# IRComms.net
KiCad netlist of a schematic drawn in Altium Designer
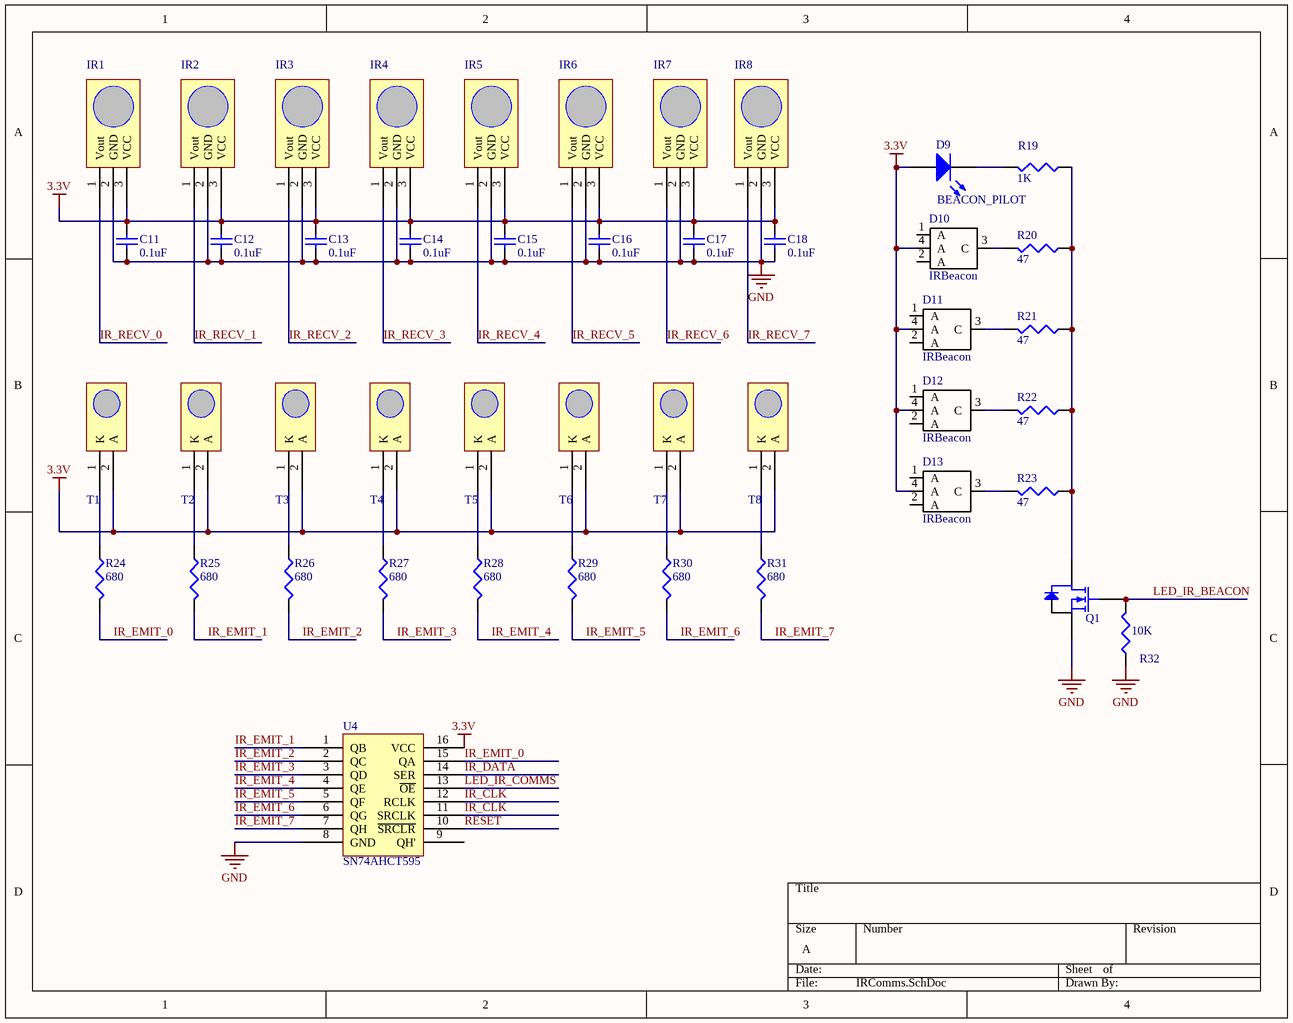
[diagram p0: IRComms.SchDoc]

(export (version "E")
  (design (tool "Eeschema 10.0.6"))
  (components
    (comp (ref "C11")
      (value "0.1uF")
      (footprint "CAPC1005L")
      (description "Capacitor (Semiconductor SIM Model)")
      (fields (field (name "Comment") "Cap Semi") (field (name "PUBLISHER") "Altium Limited"))
      (libsource (lib "Miscellaneous Devices") (part "Cap Semi"))
    )
    (comp (ref "C12")
      (value "0.1uF")
      (footprint "CAPC1005L")
      (description "Capacitor (Semiconductor SIM Model)")
      (fields (field (name "Comment") "Cap Semi") (field (name "PUBLISHER") "Altium Limited"))
      (libsource (lib "Miscellaneous Devices") (part "Cap Semi"))
    )
    (comp (ref "C13")
      (value "0.1uF")
      (footprint "CAPC1005L")
      (description "Capacitor (Semiconductor SIM Model)")
      (fields (field (name "Comment") "Cap Semi") (field (name "PUBLISHER") "Altium Limited"))
      (libsource (lib "Miscellaneous Devices") (part "Cap Semi"))
    )
    (comp (ref "C14")
      (value "0.1uF")
      (footprint "CAPC1005L")
      (description "Capacitor (Semiconductor SIM Model)")
      (fields (field (name "Comment") "Cap Semi") (field (name "PUBLISHER") "Altium Limited"))
      (libsource (lib "Miscellaneous Devices") (part "Cap Semi"))
    )
    (comp (ref "C15")
      (value "0.1uF")
      (footprint "CAPC1005L")
      (description "Capacitor (Semiconductor SIM Model)")
      (fields (field (name "Comment") "Cap Semi") (field (name "PUBLISHER") "Altium Limited"))
      (libsource (lib "Miscellaneous Devices") (part "Cap Semi"))
    )
    (comp (ref "C16")
      (value "0.1uF")
      (footprint "CAPC1005L")
      (description "Capacitor (Semiconductor SIM Model)")
      (fields (field (name "Comment") "Cap Semi") (field (name "PUBLISHER") "Altium Limited"))
      (libsource (lib "Miscellaneous Devices") (part "Cap Semi"))
    )
    (comp (ref "C17")
      (value "0.1uF")
      (footprint "CAPC1005L")
      (description "Capacitor (Semiconductor SIM Model)")
      (fields (field (name "Comment") "Cap Semi") (field (name "PUBLISHER") "Altium Limited"))
      (libsource (lib "Miscellaneous Devices") (part "Cap Semi"))
    )
    (comp (ref "C18")
      (value "0.1uF")
      (footprint "CAPC1005L")
      (description "Capacitor (Semiconductor SIM Model)")
      (fields (field (name "Comment") "Cap Semi") (field (name "PUBLISHER") "Altium Limited"))
      (libsource (lib "Miscellaneous Devices") (part "Cap Semi"))
    )
    (comp (ref "D9")
      (value "BEACON_PILOT")
      (footprint "SurfaceMount(603)")
      (libsource (lib "mrone") (part "LED"))
    )
    (comp (ref "D10") (value "IRBeacon") (footprint "IRBeacon") (libsource (lib "mrone") (part "IRBeacon")))
    (comp (ref "D11") (value "IRBeacon") (footprint "IRBeacon") (libsource (lib "mrone") (part "IRBeacon")))
    (comp (ref "D12") (value "IRBeacon") (footprint "IRBeacon") (libsource (lib "mrone") (part "IRBeacon")))
    (comp (ref "D13") (value "IRBeacon") (footprint "IRBeacon") (libsource (lib "mrone") (part "IRBeacon")))
    (comp (ref "IR1")
      (value "GP1UX31QS")
      (footprint "GP1UX31QS")
      (libsource (lib "mrone") (part "GP1UX31QS"))
    )
    (comp (ref "IR2")
      (value "GP1UX31QS")
      (footprint "GP1UX31QS")
      (libsource (lib "mrone") (part "GP1UX31QS"))
    )
    (comp (ref "IR3")
      (value "GP1UX31QS")
      (footprint "GP1UX31QS")
      (libsource (lib "mrone") (part "GP1UX31QS"))
    )
    (comp (ref "IR4")
      (value "GP1UX31QS")
      (footprint "GP1UX31QS")
      (libsource (lib "mrone") (part "GP1UX31QS"))
    )
    (comp (ref "IR5")
      (value "GP1UX31QS")
      (footprint "GP1UX31QS")
      (libsource (lib "mrone") (part "GP1UX31QS"))
    )
    (comp (ref "IR6")
      (value "GP1UX31QS")
      (footprint "GP1UX31QS")
      (libsource (lib "mrone") (part "GP1UX31QS"))
    )
    (comp (ref "IR7")
      (value "GP1UX31QS")
      (footprint "GP1UX31QS")
      (libsource (lib "mrone") (part "GP1UX31QS"))
    )
    (comp (ref "IR8")
      (value "GP1UX31QS")
      (footprint "GP1UX31QS")
      (libsource (lib "mrone") (part "GP1UX31QS"))
    )
    (comp (ref "Q1") (value "Mosfet") (footprint "SOT-23") (libsource (lib "mrone") (part "Mosfet")))
    (comp (ref "R19")
      (value "1K")
      (footprint "RESC1608L")
      (description "Resistor")
      (fields (field (name "Comment") "Res3") (field (name "PUBLISHER") "Altium Limited"))
      (libsource (lib "Miscellaneous Devices") (part "Res3"))
    )
    (comp (ref "R20")
      (value "47")
      (footprint "RESC1608L")
      (description "Resistor")
      (fields (field (name "Comment") "Res3") (field (name "PUBLISHER") "Altium Limited"))
      (libsource (lib "Miscellaneous Devices") (part "Res3"))
    )
    (comp (ref "R21")
      (value "47")
      (footprint "RESC1608L")
      (description "Resistor")
      (fields (field (name "Comment") "Res3") (field (name "PUBLISHER") "Altium Limited"))
      (libsource (lib "Miscellaneous Devices") (part "Res3"))
    )
    (comp (ref "R22")
      (value "47")
      (footprint "RESC1608L")
      (description "Resistor")
      (fields (field (name "Comment") "Res3") (field (name "PUBLISHER") "Altium Limited"))
      (libsource (lib "Miscellaneous Devices") (part "Res3"))
    )
    (comp (ref "R23")
      (value "47")
      (footprint "RESC1608L")
      (description "Resistor")
      (fields (field (name "Comment") "Res3") (field (name "PUBLISHER") "Altium Limited"))
      (libsource (lib "Miscellaneous Devices") (part "Res3"))
    )
    (comp (ref "R24")
      (value "680")
      (footprint "RESC1608L")
      (description "Resistor")
      (fields (field (name "Comment") "Res3") (field (name "PUBLISHER") "Altium Limited"))
      (libsource (lib "Miscellaneous Devices") (part "Res3"))
    )
    (comp (ref "R25")
      (value "680")
      (footprint "RESC1608L")
      (description "Resistor")
      (fields (field (name "Comment") "Res3") (field (name "PUBLISHER") "Altium Limited"))
      (libsource (lib "Miscellaneous Devices") (part "Res3"))
    )
    (comp (ref "R26")
      (value "680")
      (footprint "RESC1608L")
      (description "Resistor")
      (fields (field (name "Comment") "Res3") (field (name "PUBLISHER") "Altium Limited"))
      (libsource (lib "Miscellaneous Devices") (part "Res3"))
    )
    (comp (ref "R27")
      (value "680")
      (footprint "RESC1608L")
      (description "Resistor")
      (fields (field (name "Comment") "Res3") (field (name "PUBLISHER") "Altium Limited"))
      (libsource (lib "Miscellaneous Devices") (part "Res3"))
    )
    (comp (ref "R28")
      (value "680")
      (footprint "RESC1608L")
      (description "Resistor")
      (fields (field (name "Comment") "Res3") (field (name "PUBLISHER") "Altium Limited"))
      (libsource (lib "Miscellaneous Devices") (part "Res3"))
    )
    (comp (ref "R29")
      (value "680")
      (footprint "RESC1608L")
      (description "Resistor")
      (fields (field (name "Comment") "Res3") (field (name "PUBLISHER") "Altium Limited"))
      (libsource (lib "Miscellaneous Devices") (part "Res3"))
    )
    (comp (ref "R30")
      (value "680")
      (footprint "RESC1608L")
      (description "Resistor")
      (fields (field (name "Comment") "Res3") (field (name "PUBLISHER") "Altium Limited"))
      (libsource (lib "Miscellaneous Devices") (part "Res3"))
    )
    (comp (ref "R31")
      (value "680")
      (footprint "RESC1608L")
      (description "Resistor")
      (fields (field (name "Comment") "Res3") (field (name "PUBLISHER") "Altium Limited"))
      (libsource (lib "Miscellaneous Devices") (part "Res3"))
    )
    (comp (ref "R32")
      (value "10K")
      (footprint "RESC1608L")
      (description "Resistor")
      (fields (field (name "Comment") "Res3") (field (name "PUBLISHER") "Altium Limited"))
      (libsource (lib "Miscellaneous Devices") (part "Res3"))
    )
    (comp (ref "T1") (value "LN54") (footprint "LN54") (libsource (lib "mrone") (part "LN54")))
    (comp (ref "T2") (value "LN54") (footprint "LN54") (libsource (lib "mrone") (part "LN54")))
    (comp (ref "T3") (value "LN54") (footprint "LN54") (libsource (lib "mrone") (part "LN54")))
    (comp (ref "T4") (value "LN54") (footprint "LN54") (libsource (lib "mrone") (part "LN54")))
    (comp (ref "T5") (value "LN54") (footprint "LN54") (libsource (lib "mrone") (part "LN54")))
    (comp (ref "T6") (value "LN54") (footprint "LN54") (libsource (lib "mrone") (part "LN54")))
    (comp (ref "T7") (value "LN54") (footprint "LN54") (libsource (lib "mrone") (part "LN54")))
    (comp (ref "T8") (value "LN54") (footprint "LN54") (libsource (lib "mrone") (part "LN54")))
    (comp (ref "U4")
      (value "SN74AHCT595")
      (footprint "TSSOP-16")
      (description "shift register")
      (libsource (lib "mrone") (part "SN74AHCT595"))
    )
  )
  (nets
    (net (code "1") (name "/IR_CLK") (class "Default")
      (node (ref "U4") (pin "11") (pinfunction "SRCLK_11") (pintype "passive"))
      (node (ref "U4") (pin "12") (pinfunction "RCLK_12") (pintype "passive"))
    )
    (net (code "2") (name "/IR_DATA") (class "Default")
      (node (ref "U4") (pin "14") (pinfunction "SER_14") (pintype "passive"))
    )
    (net (code "3") (name "/IR_EMIT_0") (class "Default")
      (node (ref "R24") (pin "2") (pinfunction "2_2") (pintype "passive"))
      (node (ref "U4") (pin "15") (pinfunction "QA_15") (pintype "passive"))
    )
    (net (code "4") (name "/IR_EMIT_1") (class "Default")
      (node (ref "R25") (pin "2") (pinfunction "2_2") (pintype "passive"))
      (node (ref "U4") (pin "1") (pinfunction "QB_1") (pintype "passive"))
    )
    (net (code "5") (name "/IR_EMIT_2") (class "Default")
      (node (ref "R26") (pin "2") (pinfunction "2_2") (pintype "passive"))
      (node (ref "U4") (pin "2") (pinfunction "QC_2") (pintype "passive"))
    )
    (net (code "6") (name "/IR_EMIT_3") (class "Default")
      (node (ref "R27") (pin "2") (pinfunction "2_2") (pintype "passive"))
      (node (ref "U4") (pin "3") (pinfunction "QD_3") (pintype "passive"))
    )
    (net (code "7") (name "/IR_EMIT_4") (class "Default")
      (node (ref "R28") (pin "2") (pinfunction "2_2") (pintype "passive"))
      (node (ref "U4") (pin "4") (pinfunction "QE_4") (pintype "passive"))
    )
    (net (code "8") (name "/IR_EMIT_5") (class "Default")
      (node (ref "R29") (pin "2") (pinfunction "2_2") (pintype "passive"))
      (node (ref "U4") (pin "5") (pinfunction "QF_5") (pintype "passive"))
    )
    (net (code "9") (name "/IR_EMIT_6") (class "Default")
      (node (ref "R30") (pin "2") (pinfunction "2_2") (pintype "passive"))
      (node (ref "U4") (pin "6") (pinfunction "QG_6") (pintype "passive"))
    )
    (net (code "10") (name "/IR_EMIT_7") (class "Default")
      (node (ref "R31") (pin "2") (pinfunction "2_2") (pintype "passive"))
      (node (ref "U4") (pin "7") (pinfunction "QH_7") (pintype "passive"))
    )
    (net (code "11") (name "/IR_RECV_0") (class "Default")
      (node (ref "IR1") (pin "1") (pinfunction "Vout_1") (pintype "passive"))
    )
    (net (code "12") (name "/IR_RECV_1") (class "Default")
      (node (ref "IR2") (pin "1") (pinfunction "Vout_1") (pintype "passive"))
    )
    (net (code "13") (name "/IR_RECV_2") (class "Default")
      (node (ref "IR3") (pin "1") (pinfunction "Vout_1") (pintype "passive"))
    )
    (net (code "14") (name "/IR_RECV_3") (class "Default")
      (node (ref "IR4") (pin "1") (pinfunction "Vout_1") (pintype "passive"))
    )
    (net (code "15") (name "/IR_RECV_4") (class "Default")
      (node (ref "IR5") (pin "1") (pinfunction "Vout_1") (pintype "passive"))
    )
    (net (code "16") (name "/IR_RECV_5") (class "Default")
      (node (ref "IR6") (pin "1") (pinfunction "Vout_1") (pintype "passive"))
    )
    (net (code "17") (name "/IR_RECV_6") (class "Default")
      (node (ref "IR7") (pin "1") (pinfunction "Vout_1") (pintype "passive"))
    )
    (net (code "18") (name "/IR_RECV_7") (class "Default")
      (node (ref "IR8") (pin "1") (pinfunction "Vout_1") (pintype "passive"))
    )
    (net (code "19") (name "/LED_IR_BEACON") (class "Default")
      (node (ref "Q1") (pin "1") (pinfunction "G_1") (pintype "passive"))
      (node (ref "R32") (pin "2") (pinfunction "2_2") (pintype "passive"))
    )
    (net (code "20") (name "/LED_IR_COMMS") (class "Default")
      (node (ref "U4") (pin "13") (pinfunction "~{OE}_13") (pintype "passive"))
    )
    (net (code "21") (name "/RESET") (class "Default")
      (node (ref "U4") (pin "10") (pinfunction "~{SRCLR}_10") (pintype "passive"))
    )
    (net (code "22") (name "3.3V") (class "Default")
      (node (ref "C11") (pin "2") (pinfunction "2_2") (pintype "passive"))
      (node (ref "C12") (pin "2") (pinfunction "2_2") (pintype "passive"))
      (node (ref "C13") (pin "2") (pinfunction "2_2") (pintype "passive"))
      (node (ref "C14") (pin "2") (pinfunction "2_2") (pintype "passive"))
      (node (ref "C15") (pin "2") (pinfunction "2_2") (pintype "passive"))
      (node (ref "C16") (pin "2") (pinfunction "2_2") (pintype "passive"))
      (node (ref "C17") (pin "2") (pinfunction "2_2") (pintype "passive"))
      (node (ref "C18") (pin "2") (pinfunction "2_2") (pintype "passive"))
      (node (ref "D10") (pin "4") (pinfunction "A_4") (pintype "passive"))
      (node (ref "D11") (pin "4") (pinfunction "A_4") (pintype "passive"))
      (node (ref "D12") (pin "4") (pinfunction "A_4") (pintype "passive"))
      (node (ref "D13") (pin "4") (pinfunction "A_4") (pintype "passive"))
      (node (ref "D9") (pin "1") (pinfunction "A_1") (pintype "passive"))
      (node (ref "IR1") (pin "3") (pinfunction "VCC_3") (pintype "power_in"))
      (node (ref "IR2") (pin "3") (pinfunction "VCC_3") (pintype "power_in"))
      (node (ref "IR3") (pin "3") (pinfunction "VCC_3") (pintype "power_in"))
      (node (ref "IR4") (pin "3") (pinfunction "VCC_3") (pintype "power_in"))
      (node (ref "IR5") (pin "3") (pinfunction "VCC_3") (pintype "power_in"))
      (node (ref "IR6") (pin "3") (pinfunction "VCC_3") (pintype "power_in"))
      (node (ref "IR7") (pin "3") (pinfunction "VCC_3") (pintype "power_in"))
      (node (ref "IR8") (pin "3") (pinfunction "VCC_3") (pintype "power_in"))
      (node (ref "T1") (pin "2") (pinfunction "A_2") (pintype "passive"))
      (node (ref "T2") (pin "2") (pinfunction "A_2") (pintype "passive"))
      (node (ref "T3") (pin "2") (pinfunction "A_2") (pintype "passive"))
      (node (ref "T4") (pin "2") (pinfunction "A_2") (pintype "passive"))
      (node (ref "T5") (pin "2") (pinfunction "A_2") (pintype "passive"))
      (node (ref "T6") (pin "2") (pinfunction "A_2") (pintype "passive"))
      (node (ref "T7") (pin "2") (pinfunction "A_2") (pintype "passive"))
      (node (ref "T8") (pin "2") (pinfunction "A_2") (pintype "passive"))
      (node (ref "U4") (pin "16") (pinfunction "VCC_16") (pintype "passive"))
    )
    (net (code "23") (name "GND") (class "Default")
      (node (ref "C11") (pin "1") (pinfunction "1_1") (pintype "passive"))
      (node (ref "C12") (pin "1") (pinfunction "1_1") (pintype "passive"))
      (node (ref "C13") (pin "1") (pinfunction "1_1") (pintype "passive"))
      (node (ref "C14") (pin "1") (pinfunction "1_1") (pintype "passive"))
      (node (ref "C15") (pin "1") (pinfunction "1_1") (pintype "passive"))
      (node (ref "C16") (pin "1") (pinfunction "1_1") (pintype "passive"))
      (node (ref "C17") (pin "1") (pinfunction "1_1") (pintype "passive"))
      (node (ref "C18") (pin "1") (pinfunction "1_1") (pintype "passive"))
      (node (ref "IR1") (pin "2") (pinfunction "GND_2") (pintype "power_in"))
      (node (ref "IR2") (pin "2") (pinfunction "GND_2") (pintype "power_in"))
      (node (ref "IR3") (pin "2") (pinfunction "GND_2") (pintype "power_in"))
      (node (ref "IR4") (pin "2") (pinfunction "GND_2") (pintype "power_in"))
      (node (ref "IR5") (pin "2") (pinfunction "GND_2") (pintype "power_in"))
      (node (ref "IR6") (pin "2") (pinfunction "GND_2") (pintype "power_in"))
      (node (ref "IR7") (pin "2") (pinfunction "GND_2") (pintype "power_in"))
      (node (ref "IR8") (pin "2") (pinfunction "GND_2") (pintype "power_in"))
      (node (ref "Q1") (pin "2") (pinfunction "S_2") (pintype "passive"))
      (node (ref "R32") (pin "1") (pinfunction "1_1") (pintype "passive"))
      (node (ref "U4") (pin "8") (pinfunction "GND_8") (pintype "passive"))
    )
    (net (code "24") (name "Net-(D9-K)") (class "Default")
      (node (ref "D9") (pin "2") (pinfunction "K_2") (pintype "passive"))
      (node (ref "R19") (pin "2") (pinfunction "2_2") (pintype "passive"))
    )
    (net (code "25") (name "Net-(D10-C)") (class "Default")
      (node (ref "D10") (pin "3") (pinfunction "C_3") (pintype "passive"))
      (node (ref "R20") (pin "2") (pinfunction "2_2") (pintype "passive"))
    )
    (net (code "26") (name "Net-(D11-C)") (class "Default")
      (node (ref "D11") (pin "3") (pinfunction "C_3") (pintype "passive"))
      (node (ref "R21") (pin "2") (pinfunction "2_2") (pintype "passive"))
    )
    (net (code "27") (name "Net-(D12-C)") (class "Default")
      (node (ref "D12") (pin "3") (pinfunction "C_3") (pintype "passive"))
      (node (ref "R22") (pin "2") (pinfunction "2_2") (pintype "passive"))
    )
    (net (code "28") (name "Net-(D13-C)") (class "Default")
      (node (ref "D13") (pin "3") (pinfunction "C_3") (pintype "passive"))
      (node (ref "R23") (pin "2") (pinfunction "2_2") (pintype "passive"))
    )
    (net (code "29") (name "Net-(Q1-D)") (class "Default")
      (node (ref "Q1") (pin "3") (pinfunction "D_3") (pintype "passive"))
      (node (ref "R19") (pin "1") (pinfunction "1_1") (pintype "passive"))
      (node (ref "R20") (pin "1") (pinfunction "1_1") (pintype "passive"))
      (node (ref "R21") (pin "1") (pinfunction "1_1") (pintype "passive"))
      (node (ref "R22") (pin "1") (pinfunction "1_1") (pintype "passive"))
      (node (ref "R23") (pin "1") (pinfunction "1_1") (pintype "passive"))
    )
    (net (code "30") (name "Net-(T1-K)") (class "Default")
      (node (ref "R24") (pin "1") (pinfunction "1_1") (pintype "passive"))
      (node (ref "T1") (pin "1") (pinfunction "K_1") (pintype "passive"))
    )
    (net (code "31") (name "Net-(T2-K)") (class "Default")
      (node (ref "R25") (pin "1") (pinfunction "1_1") (pintype "passive"))
      (node (ref "T2") (pin "1") (pinfunction "K_1") (pintype "passive"))
    )
    (net (code "32") (name "Net-(T3-K)") (class "Default")
      (node (ref "R26") (pin "1") (pinfunction "1_1") (pintype "passive"))
      (node (ref "T3") (pin "1") (pinfunction "K_1") (pintype "passive"))
    )
    (net (code "33") (name "Net-(T4-K)") (class "Default")
      (node (ref "R27") (pin "1") (pinfunction "1_1") (pintype "passive"))
      (node (ref "T4") (pin "1") (pinfunction "K_1") (pintype "passive"))
    )
    (net (code "34") (name "Net-(T5-K)") (class "Default")
      (node (ref "R28") (pin "1") (pinfunction "1_1") (pintype "passive"))
      (node (ref "T5") (pin "1") (pinfunction "K_1") (pintype "passive"))
    )
    (net (code "35") (name "Net-(T6-K)") (class "Default")
      (node (ref "R29") (pin "1") (pinfunction "1_1") (pintype "passive"))
      (node (ref "T6") (pin "1") (pinfunction "K_1") (pintype "passive"))
    )
    (net (code "36") (name "Net-(T7-K)") (class "Default")
      (node (ref "R30") (pin "1") (pinfunction "1_1") (pintype "passive"))
      (node (ref "T7") (pin "1") (pinfunction "K_1") (pintype "passive"))
    )
    (net (code "37") (name "Net-(T8-K)") (class "Default")
      (node (ref "R31") (pin "1") (pinfunction "1_1") (pintype "passive"))
      (node (ref "T8") (pin "1") (pinfunction "K_1") (pintype "passive"))
    )
    (net (code "38") (name "unconnected-(D10-A-Pad1)") (class "Default")
      (node (ref "D10") (pin "1") (pinfunction "A_1") (pintype "passive"))
    )
    (net (code "39") (name "unconnected-(D10-A-Pad2)") (class "Default")
      (node (ref "D10") (pin "2") (pinfunction "A_2") (pintype "passive"))
    )
    (net (code "40") (name "unconnected-(D11-A-Pad1)") (class "Default")
      (node (ref "D11") (pin "1") (pinfunction "A_1") (pintype "passive"))
    )
    (net (code "41") (name "unconnected-(D11-A-Pad2)") (class "Default")
      (node (ref "D11") (pin "2") (pinfunction "A_2") (pintype "passive"))
    )
    (net (code "42") (name "unconnected-(D12-A-Pad1)") (class "Default")
      (node (ref "D12") (pin "1") (pinfunction "A_1") (pintype "passive"))
    )
    (net (code "43") (name "unconnected-(D12-A-Pad2)") (class "Default")
      (node (ref "D12") (pin "2") (pinfunction "A_2") (pintype "passive"))
    )
    (net (code "44") (name "unconnected-(D13-A-Pad1)") (class "Default")
      (node (ref "D13") (pin "1") (pinfunction "A_1") (pintype "passive"))
    )
    (net (code "45") (name "unconnected-(D13-A-Pad2)") (class "Default")
      (node (ref "D13") (pin "2") (pinfunction "A_2") (pintype "passive"))
    )
    (net (code "46") (name "unconnected-(U4-QH'-Pad9)") (class "Default")
      (node (ref "U4") (pin "9") (pinfunction "QH'_9") (pintype "passive"))
    )
  )
)
